# estop_rx.net
KiCad netlist of a schematic drawn in EAGLE
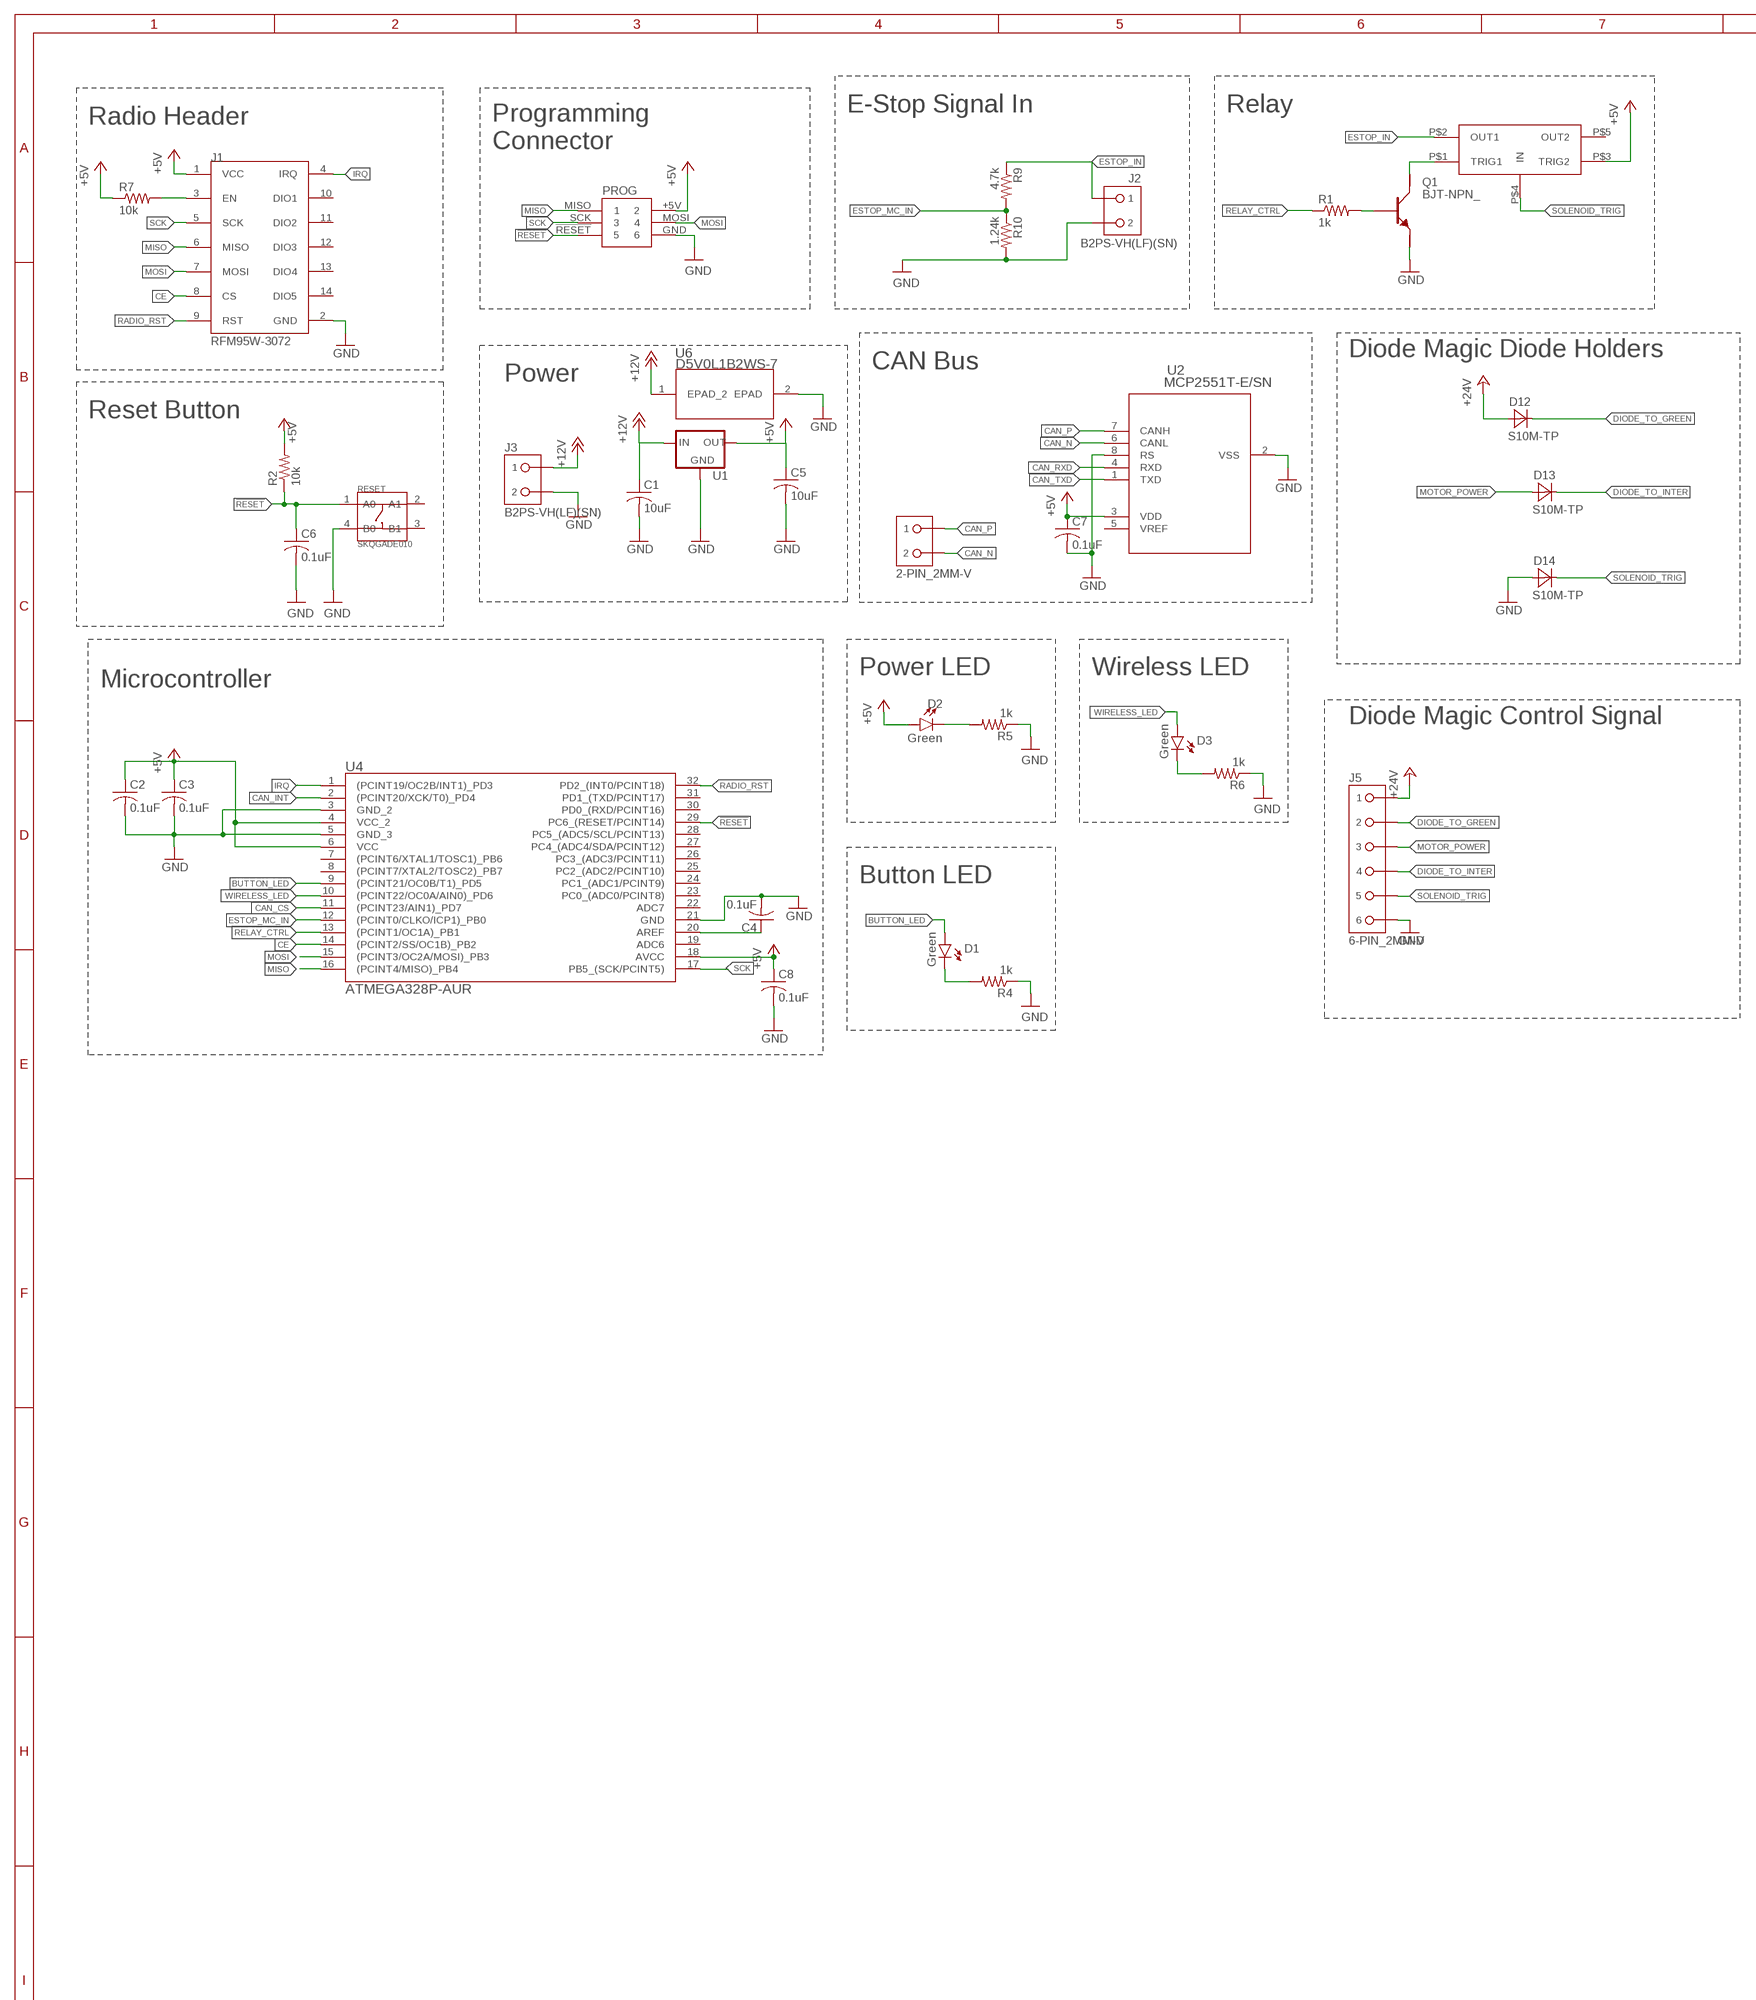
[diagram p0: schematic, sheet 1, part 1 of 2]
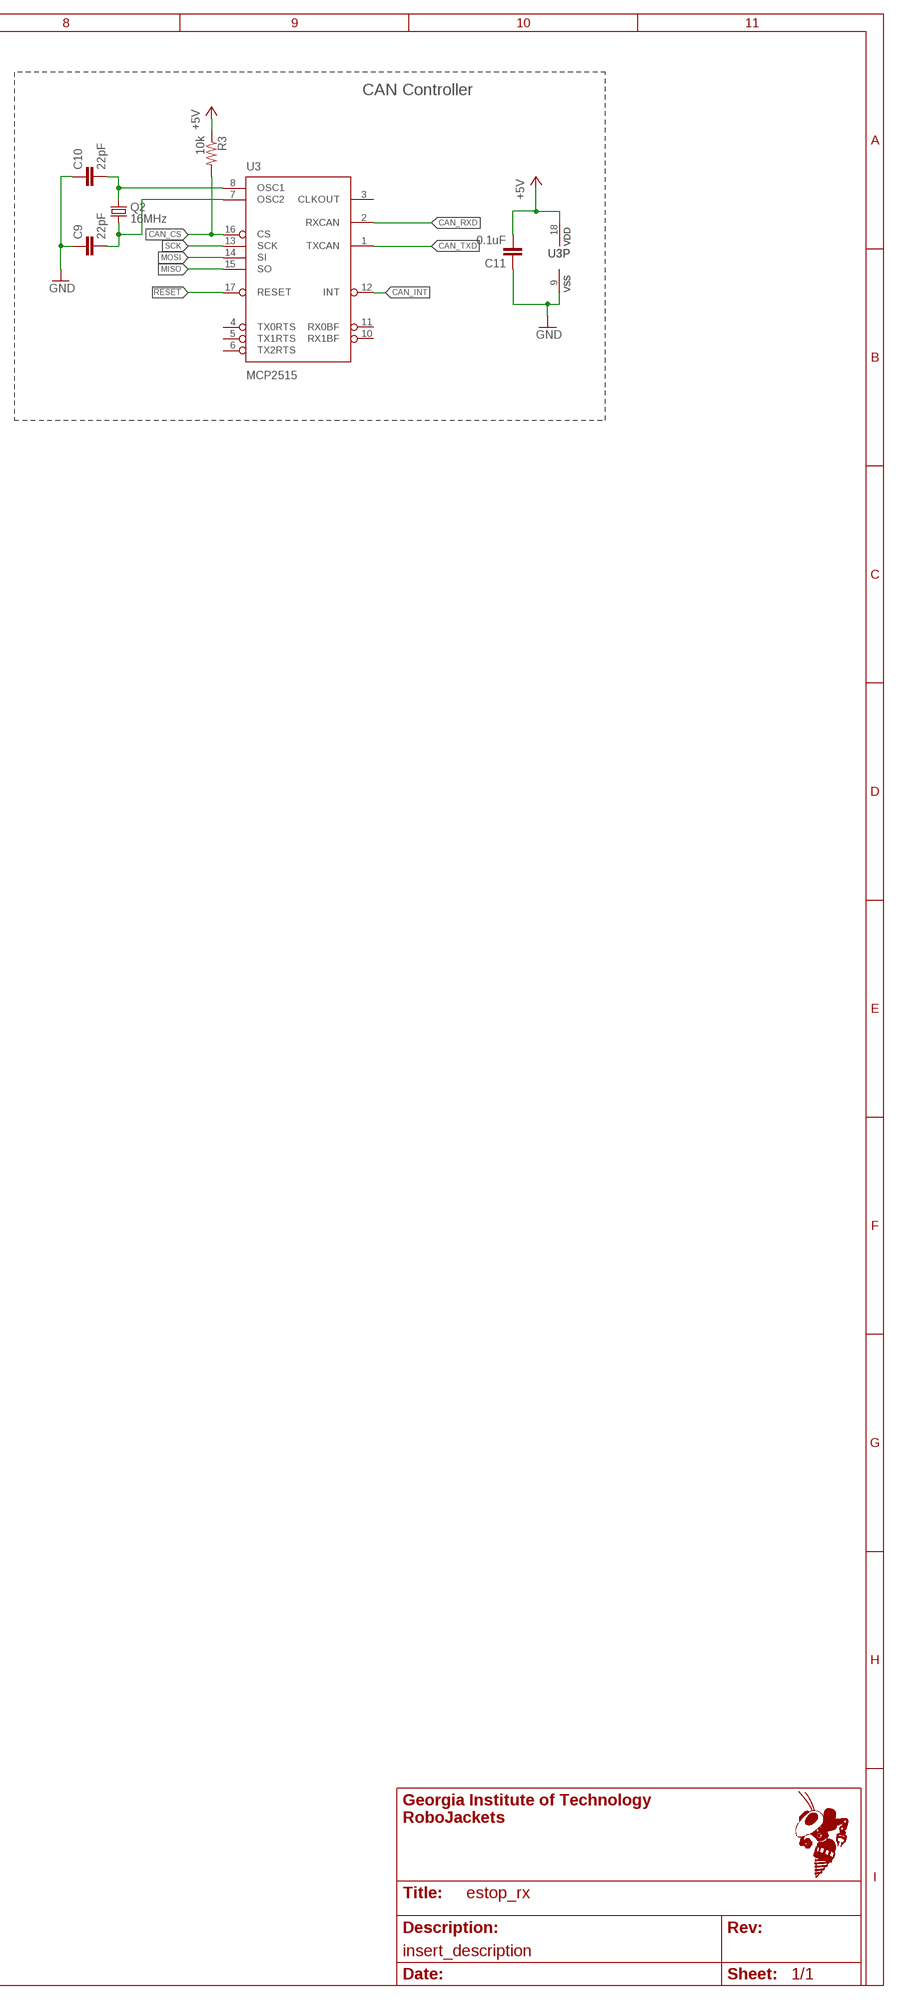
[diagram p1: schematic, sheet 1, part 2 of 2]

(export (version "E")
  (design (tool "Eeschema 10.0.6"))
  (components
    (comp (ref "C1")
      (value "10uF")
      (footprint "eagle-import:C0805")
      (libsource (lib "eagle-import") (part "C-USC0805"))
    )
    (comp (ref "C2")
      (value "0.1uF")
      (footprint "eagle-import:C0603")
      (libsource (lib "eagle-import") (part "C-USC0603"))
    )
    (comp (ref "C3")
      (value "0.1uF")
      (footprint "eagle-import:C0603")
      (libsource (lib "eagle-import") (part "C-USC0603"))
    )
    (comp (ref "C4")
      (value "0.1uF")
      (footprint "eagle-import:C0603")
      (libsource (lib "eagle-import") (part "C-USC0603"))
    )
    (comp (ref "C5")
      (value "10uF")
      (footprint "eagle-import:C0805")
      (libsource (lib "eagle-import") (part "C-USC0805"))
    )
    (comp (ref "C6")
      (value "0.1uF")
      (footprint "eagle-import:C0603")
      (libsource (lib "eagle-import") (part "resistor_348_C-USC0603"))
    )
    (comp (ref "C7")
      (value "0.1uF")
      (footprint "eagle-import:C0603")
      (libsource (lib "eagle-import") (part "C-USC0603"))
    )
    (comp (ref "C8")
      (value "0.1uF")
      (footprint "eagle-import:C0603")
      (libsource (lib "eagle-import") (part "C-USC0603"))
    )
    (comp (ref "C9")
      (value "22pF")
      (footprint "eagle-import:0603-CAP")
      (libsource (lib "eagle-import") (part "22PF-50V-5%(0603)"))
    )
    (comp (ref "C10")
      (value "22pF")
      (footprint "eagle-import:0603-CAP")
      (libsource (lib "eagle-import") (part "22PF-50V-5%(0603)"))
    )
    (comp (ref "C11")
      (value "0.1uF")
      (footprint "eagle-import:0603-CAP")
      (libsource (lib "eagle-import") (part "0.1UF-25V(+80/-20%)(0603)"))
    )
    (comp (ref "D1")
      (value "Green")
      (footprint "eagle-import:LED-0603")
      (libsource (lib "eagle-import") (part "LED-YELLOW0603"))
    )
    (comp (ref "D2")
      (value "Green")
      (footprint "eagle-import:LED-0603")
      (libsource (lib "eagle-import") (part "LED-YELLOW0603"))
    )
    (comp (ref "D3")
      (value "Green")
      (footprint "eagle-import:LED-0603")
      (libsource (lib "eagle-import") (part "LED-YELLOW0603"))
    )
    (comp (ref "D12")
      (value "S10M-TP")
      (footprint "eagle-import:SMC")
      (libsource (lib "eagle-import") (part "S10M-TP"))
    )
    (comp (ref "D13")
      (value "S10M-TP")
      (footprint "eagle-import:SMC")
      (libsource (lib "eagle-import") (part "S10M-TP"))
    )
    (comp (ref "D14")
      (value "S10M-TP")
      (footprint "eagle-import:SMC")
      (libsource (lib "eagle-import") (part "S10M-TP"))
    )
    (comp (ref "J1")
      (value "RFM95W-3072")
      (footprint "eagle-import:RFM95W-3072")
      (libsource (lib "eagle-import") (part "RFM95W-3072"))
    )
    (comp (ref "J2")
      (value "B2PS-VH(LF)(SN)")
      (footprint "eagle-import:B2PS-CENTERED")
      (libsource (lib "eagle-import") (part "B2P?-VH(LF)(SN)S"))
    )
    (comp (ref "J3")
      (value "B2PS-VH(LF)(SN)")
      (footprint "eagle-import:B2PS-CENTERED")
      (libsource (lib "eagle-import") (part "B2P?-VH(LF)(SN)S"))
    )
    (comp (ref "J4")
      (value "2-PIN_2MM-V")
      (footprint "eagle-import:2MM-2-V")
      (libsource (lib "eagle-import") (part "2-PIN_2MM-V"))
    )
    (comp (ref "J5")
      (value "6-PIN_2MM-V")
      (footprint "eagle-import:2MM-6-V")
      (libsource (lib "eagle-import") (part "6-PIN_2MM-V"))
    )
    (comp (ref "PROG")
      (value "ICSP Connector")
      (footprint "eagle-import:2X3SHROUDED")
      (libsource (lib "eagle-import") (part "2X3SHROUDED"))
    )
    (comp (ref "Q1")
      (value "BJT-NPN_")
      (footprint "eagle-import:SOT-23-3")
      (libsource (lib "eagle-import") (part "BJT-NPN_"))
    )
    (comp (ref "Q2")
      (value "16MHz")
      (footprint "eagle-import:CRYSTAL-SMD-5X3")
      (libsource (lib "eagle-import") (part "CRYSTAL5X3"))
    )
    (comp (ref "R1")
      (value "1k")
      (footprint "eagle-import:R0603")
      (libsource (lib "eagle-import") (part "R-US_R0603"))
    )
    (comp (ref "R2")
      (value "10k")
      (footprint "eagle-import:R0603")
      (libsource (lib "eagle-import") (part "R-US_R0603"))
    )
    (comp (ref "R3")
      (value "10k")
      (footprint "eagle-import:R0603")
      (libsource (lib "eagle-import") (part "resistor_348_R-US_R0603"))
    )
    (comp (ref "R4")
      (value "1k")
      (footprint "eagle-import:R0603")
      (libsource (lib "eagle-import") (part "resistor_348_R-US_R0603"))
    )
    (comp (ref "R5")
      (value "1k")
      (footprint "eagle-import:R0603")
      (libsource (lib "eagle-import") (part "resistor_348_R-US_R0603"))
    )
    (comp (ref "R6")
      (value "1k")
      (footprint "eagle-import:R0603")
      (libsource (lib "eagle-import") (part "resistor_348_R-US_R0603"))
    )
    (comp (ref "R7")
      (value "10k")
      (footprint "eagle-import:R0603")
      (libsource (lib "eagle-import") (part "R-US_R0603"))
    )
    (comp (ref "R9")
      (value "4.7k")
      (footprint "eagle-import:R0603")
      (libsource (lib "eagle-import") (part "resistor_348_R-US_R0603"))
    )
    (comp (ref "R10")
      (value "1.24k")
      (footprint "eagle-import:R0603")
      (libsource (lib "eagle-import") (part "resistor_348_R-US_R0603"))
    )
    (comp (ref "RESET")
      (value "SKQGADE010")
      (footprint "eagle-import:SW4-SMD-5.2X5.2X1.5MM")
      (libsource (lib "eagle-import") (part "SMD-SWITCH-TOP-260GF(4P-D5.2MM)"))
    )
    (comp (ref "U$1")
      (value "G5LE-14")
      (footprint "eagle-import:G5LE-14")
      (libsource (lib "eagle-import") (part "G5LE-14"))
    )
    (comp (ref "U1")
      (value "R-78E5.0-1.0CONV_R-78E5.0-1.0")
      (footprint "eagle-import:CONV_R-78E5.0-1.0")
      (libsource (lib "eagle-import") (part "R-78E5.0-1.0CONV_R-78E5.0-1.0"))
    )
    (comp (ref "U2")
      (value "MCP2551T-E/SN")
      (footprint "eagle-import:SOIC8-N_MC")
      (fields (field (name "MANUFACTURER_PART_NUMBER") "MCP2551TESN"))
      (libsource (lib "eagle-import") (part "MCP2551T-E/SN"))
    )
    (comp (ref "U3")
      (value "MCP2515")
      (footprint "eagle-import:SO-18W")
      (libsource (lib "eagle-import") (part "MCP2510SO"))
    )
    (comp (ref "U4")
      (value "ATMEGA328P-AUR")
      (footprint "eagle-import:ATMEGA328P-AUR")
      (libsource (lib "eagle-import") (part "ATMEGA328P-AUR"))
    )
    (comp (ref "U6")
      (value "D5V0L1B2WS-7")
      (footprint "eagle-import:SOD323")
      (libsource (lib "eagle-import") (part "D5V0L1B2WS-7"))
    )
  )
  (nets
    (net (code "1") (name "+5V") (class "Default")
      (node (ref "C11") (pin "2") (pinfunction "2_2") (pintype "passive"))
      (node (ref "C2") (pin "1") (pinfunction "1_1") (pintype "passive"))
      (node (ref "C3") (pin "1") (pinfunction "1_1") (pintype "passive"))
      (node (ref "C5") (pin "1") (pinfunction "1_1") (pintype "passive"))
      (node (ref "C7") (pin "1") (pinfunction "1_1") (pintype "passive"))
      (node (ref "C8") (pin "1") (pinfunction "1_1") (pintype "passive"))
      (node (ref "D2") (pin "A") (pinfunction "A_A") (pintype "passive"))
      (node (ref "J1") (pin "1") (pinfunction "VCC_1") (pintype "passive"))
      (node (ref "PROG") (pin "+5V") (pinfunction "2_+5V") (pintype "bidirectional"))
      (node (ref "R2") (pin "2") (pinfunction "2_2") (pintype "passive"))
      (node (ref "R3") (pin "1") (pinfunction "1_1") (pintype "passive"))
      (node (ref "R7") (pin "1") (pinfunction "1_1") (pintype "passive"))
      (node (ref "U$1") (pin "P$3") (pinfunction "TRIG2_P$3") (pintype "bidirectional"))
      (node (ref "U1") (pin "3") (pinfunction "OUT_3") (pintype "passive"))
      (node (ref "U2") (pin "3") (pinfunction "VDD_3") (pintype "passive"))
      (node (ref "U3") (pin "18") (pinfunction "VDD_18") (pintype "power_in"))
      (node (ref "U4") (pin "18") (pinfunction "AVCC_18") (pintype "bidirectional"))
      (node (ref "U4") (pin "4") (pinfunction "VCC_2_4") (pintype "bidirectional"))
      (node (ref "U4") (pin "6") (pinfunction "VCC_6") (pintype "bidirectional"))
    )
    (net (code "2") (name "+12V") (class "Default")
      (node (ref "C1") (pin "1") (pinfunction "1_1") (pintype "passive"))
      (node (ref "J3") (pin "1") (pinfunction "1_1") (pintype "bidirectional"))
      (node (ref "U1") (pin "1") (pinfunction "IN_1") (pintype "input"))
      (node (ref "U6") (pin "1") (pinfunction "EPAD_2_1") (pintype "passive"))
    )
    (net (code "3") (name "+24V") (class "Default")
      (node (ref "D12") (pin "A") (pinfunction "A_A") (pintype "passive"))
      (node (ref "J5") (pin "1") (pinfunction "1_1") (pintype "passive"))
    )
    (net (code "4") (name "/~{RESET}") (class "Default")
      (node (ref "C6") (pin "1") (pinfunction "1_1") (pintype "passive"))
      (node (ref "PROG") (pin "!RESET") (pinfunction "5_!RESET") (pintype "bidirectional"))
      (node (ref "R2") (pin "1") (pinfunction "1_1") (pintype "passive"))
      (node (ref "RESET") (pin "1") (pinfunction "A0_1") (pintype "bidirectional"))
      (node (ref "U3") (pin "17") (pinfunction "RESET_17") (pintype "input"))
      (node (ref "U4") (pin "29") (pinfunction "PC6_(RESET/PCINT14)_29") (pintype "bidirectional"))
    )
    (net (code "5") (name "BUTTON_LED") (class "Default")
      (node (ref "D1") (pin "A") (pinfunction "A_A") (pintype "passive"))
      (node (ref "U4") (pin "9") (pinfunction "(PCINT21/OC0B/T1)_PD5_9") (pintype "bidirectional"))
    )
    (net (code "6") (name "CAN_CS") (class "Default")
      (node (ref "R3") (pin "2") (pinfunction "2_2") (pintype "passive"))
      (node (ref "U3") (pin "16") (pinfunction "CS_16") (pintype "input"))
      (node (ref "U4") (pin "11") (pinfunction "(PCINT23/AIN1)_PD7_11") (pintype "bidirectional"))
    )
    (net (code "7") (name "CAN_INT") (class "Default")
      (node (ref "U3") (pin "12") (pinfunction "INT_12") (pintype "output"))
      (node (ref "U4") (pin "2") (pinfunction "(PCINT20/XCK/T0)_PD4_2") (pintype "bidirectional"))
    )
    (net (code "8") (name "CAN_N") (class "Default")
      (node (ref "J4") (pin "2") (pinfunction "2_2") (pintype "bidirectional"))
      (node (ref "U2") (pin "6") (pinfunction "CANL_6") (pintype "passive"))
    )
    (net (code "9") (name "CAN_P") (class "Default")
      (node (ref "J4") (pin "1") (pinfunction "1_1") (pintype "bidirectional"))
      (node (ref "U2") (pin "7") (pinfunction "CANH_7") (pintype "passive"))
    )
    (net (code "10") (name "CAN_RXD") (class "Default")
      (node (ref "U2") (pin "4") (pinfunction "RXD_4") (pintype "passive"))
      (node (ref "U3") (pin "2") (pinfunction "RXCAN_2") (pintype "input"))
    )
    (net (code "11") (name "CAN_TXD") (class "Default")
      (node (ref "U2") (pin "1") (pinfunction "TXD_1") (pintype "passive"))
      (node (ref "U3") (pin "1") (pinfunction "TXCAN_1") (pintype "output"))
    )
    (net (code "12") (name "CE") (class "Default")
      (node (ref "J1") (pin "8") (pinfunction "CS_8") (pintype "passive"))
      (node (ref "U4") (pin "14") (pinfunction "(PCINT2/SS/OC1B)_PB2_14") (pintype "bidirectional"))
    )
    (net (code "13") (name "DIODE_TO_GREEN") (class "Default")
      (node (ref "D12") (pin "C") (pinfunction "C_C") (pintype "passive"))
      (node (ref "J5") (pin "2") (pinfunction "2_2") (pintype "passive"))
    )
    (net (code "14") (name "DIODE_TO_INTER") (class "Default")
      (node (ref "D13") (pin "C") (pinfunction "C_C") (pintype "passive"))
      (node (ref "J5") (pin "4") (pinfunction "4_4") (pintype "passive"))
    )
    (net (code "15") (name "ESTOP_IN") (class "Default")
      (node (ref "J2") (pin "1") (pinfunction "1_1") (pintype "bidirectional"))
      (node (ref "R9") (pin "1") (pinfunction "1_1") (pintype "passive"))
      (node (ref "U$1") (pin "P$2") (pinfunction "OUT1_P$2") (pintype "bidirectional"))
    )
    (net (code "16") (name "ESTOP_MC_IN") (class "Default")
      (node (ref "R10") (pin "1") (pinfunction "1_1") (pintype "passive"))
      (node (ref "R9") (pin "2") (pinfunction "2_2") (pintype "passive"))
      (node (ref "U4") (pin "12") (pinfunction "(PCINT0/CLKO/ICP1)_PB0_12") (pintype "bidirectional"))
    )
    (net (code "17") (name "GND") (class "Default")
      (node (ref "C1") (pin "2") (pinfunction "2_2") (pintype "passive"))
      (node (ref "C10") (pin "1") (pinfunction "1_1") (pintype "passive"))
      (node (ref "C11") (pin "1") (pinfunction "1_1") (pintype "passive"))
      (node (ref "C2") (pin "2") (pinfunction "2_2") (pintype "passive"))
      (node (ref "C3") (pin "2") (pinfunction "2_2") (pintype "passive"))
      (node (ref "C4") (pin "2") (pinfunction "2_2") (pintype "passive"))
      (node (ref "C5") (pin "2") (pinfunction "2_2") (pintype "passive"))
      (node (ref "C6") (pin "2") (pinfunction "2_2") (pintype "passive"))
      (node (ref "C7") (pin "2") (pinfunction "2_2") (pintype "passive"))
      (node (ref "C8") (pin "2") (pinfunction "2_2") (pintype "passive"))
      (node (ref "C9") (pin "1") (pinfunction "1_1") (pintype "passive"))
      (node (ref "D14") (pin "A") (pinfunction "A_A") (pintype "passive"))
      (node (ref "J1") (pin "2") (pinfunction "GND_2") (pintype "passive"))
      (node (ref "J2") (pin "2") (pinfunction "2_2") (pintype "bidirectional"))
      (node (ref "J3") (pin "2") (pinfunction "2_2") (pintype "bidirectional"))
      (node (ref "J5") (pin "6") (pinfunction "6_6") (pintype "passive"))
      (node (ref "PROG") (pin "GND") (pinfunction "6_GND") (pintype "bidirectional"))
      (node (ref "Q1") (pin "2") (pinfunction "E_2") (pintype "bidirectional"))
      (node (ref "R10") (pin "2") (pinfunction "2_2") (pintype "passive"))
      (node (ref "R4") (pin "1") (pinfunction "1_1") (pintype "passive"))
      (node (ref "R5") (pin "1") (pinfunction "1_1") (pintype "passive"))
      (node (ref "R6") (pin "1") (pinfunction "1_1") (pintype "passive"))
      (node (ref "RESET") (pin "4") (pinfunction "B0_4") (pintype "bidirectional"))
      (node (ref "U1") (pin "2") (pinfunction "GND_2") (pintype "input"))
      (node (ref "U2") (pin "2") (pinfunction "VSS_2") (pintype "passive"))
      (node (ref "U2") (pin "8") (pinfunction "RS_8") (pintype "passive"))
      (node (ref "U3") (pin "9") (pinfunction "VSS_9") (pintype "power_in"))
      (node (ref "U4") (pin "21") (pinfunction "GND_21") (pintype "bidirectional"))
      (node (ref "U4") (pin "3") (pinfunction "GND_2_3") (pintype "bidirectional"))
      (node (ref "U4") (pin "5") (pinfunction "GND_3_5") (pintype "bidirectional"))
      (node (ref "U6") (pin "2") (pinfunction "EPAD_2") (pintype "passive"))
    )
    (net (code "18") (name "IRQ") (class "Default")
      (node (ref "J1") (pin "4") (pinfunction "IRQ_4") (pintype "passive"))
      (node (ref "U4") (pin "1") (pinfunction "(PCINT19/OC2B/INT1)_PD3_1") (pintype "bidirectional"))
    )
    (net (code "19") (name "MISO") (class "Default")
      (node (ref "J1") (pin "6") (pinfunction "MISO_6") (pintype "passive"))
      (node (ref "PROG") (pin "MISO") (pinfunction "1_MISO") (pintype "bidirectional"))
      (node (ref "U3") (pin "15") (pinfunction "SO_15") (pintype "output"))
      (node (ref "U4") (pin "16") (pinfunction "(PCINT4/MISO)_PB4_16") (pintype "bidirectional"))
    )
    (net (code "20") (name "MOSI") (class "Default")
      (node (ref "J1") (pin "7") (pinfunction "MOSI_7") (pintype "passive"))
      (node (ref "PROG") (pin "MOSI") (pinfunction "4_MOSI") (pintype "bidirectional"))
      (node (ref "U3") (pin "14") (pinfunction "SI_14") (pintype "input"))
      (node (ref "U4") (pin "15") (pinfunction "(PCINT3/OC2A/MOSI)_PB3_15") (pintype "bidirectional"))
    )
    (net (code "21") (name "MOTOR_POWER") (class "Default")
      (node (ref "D13") (pin "A") (pinfunction "A_A") (pintype "passive"))
      (node (ref "J5") (pin "3") (pinfunction "3_3") (pintype "passive"))
    )
    (net (code "22") (name "Net-(D1-PadC)") (class "Default")
      (node (ref "D1") (pin "C") (pinfunction "C_C") (pintype "passive"))
      (node (ref "R4") (pin "2") (pinfunction "2_2") (pintype "passive"))
    )
    (net (code "23") (name "Net-(D2-PadC)") (class "Default")
      (node (ref "D2") (pin "C") (pinfunction "C_C") (pintype "passive"))
      (node (ref "R5") (pin "2") (pinfunction "2_2") (pintype "passive"))
    )
    (net (code "24") (name "Net-(D3-PadC)") (class "Default")
      (node (ref "D3") (pin "C") (pinfunction "C_C") (pintype "passive"))
      (node (ref "R6") (pin "2") (pinfunction "2_2") (pintype "passive"))
    )
    (net (code "25") (name "Net-(J1-EN)") (class "Default")
      (node (ref "J1") (pin "3") (pinfunction "EN_3") (pintype "passive"))
      (node (ref "R7") (pin "2") (pinfunction "2_2") (pintype "passive"))
    )
    (net (code "26") (name "Net-(Q1-B)") (class "Default")
      (node (ref "Q1") (pin "1") (pinfunction "B_1") (pintype "bidirectional"))
      (node (ref "R1") (pin "2") (pinfunction "2_2") (pintype "passive"))
    )
    (net (code "27") (name "Net-(Q1-C)") (class "Default")
      (node (ref "Q1") (pin "3") (pinfunction "C_3") (pintype "bidirectional"))
      (node (ref "U$1") (pin "P$1") (pinfunction "TRIG1_P$1") (pintype "bidirectional"))
    )
    (net (code "28") (name "Net-(Q2-2)") (class "Default")
      (node (ref "C10") (pin "2") (pinfunction "2_2") (pintype "passive"))
      (node (ref "Q2") (pin "3") (pinfunction "2_3") (pintype "passive"))
      (node (ref "U3") (pin "8") (pinfunction "OSC1_8") (pintype "input"))
    )
    (net (code "29") (name "Net-(U3A-OSC2)") (class "Default")
      (node (ref "C9") (pin "2") (pinfunction "2_2") (pintype "passive"))
      (node (ref "Q2") (pin "1") (pinfunction "1_1") (pintype "passive"))
      (node (ref "U3") (pin "7") (pinfunction "OSC2_7") (pintype "output"))
    )
    (net (code "30") (name "Net-(U4-AREF)") (class "Default")
      (node (ref "C4") (pin "1") (pinfunction "1_1") (pintype "passive"))
      (node (ref "U4") (pin "20") (pinfunction "AREF_20") (pintype "bidirectional"))
    )
    (net (code "31") (name "RADIO_RST") (class "Default")
      (node (ref "J1") (pin "9") (pinfunction "RST_9") (pintype "passive"))
      (node (ref "U4") (pin "32") (pinfunction "PD2_(INT0/PCINT18)_32") (pintype "bidirectional"))
    )
    (net (code "32") (name "RELAY_CTRL") (class "Default")
      (node (ref "R1") (pin "1") (pinfunction "1_1") (pintype "passive"))
      (node (ref "U4") (pin "13") (pinfunction "(PCINT1/OC1A)_PB1_13") (pintype "bidirectional"))
    )
    (net (code "33") (name "SCK") (class "Default")
      (node (ref "J1") (pin "5") (pinfunction "SCK_5") (pintype "passive"))
      (node (ref "PROG") (pin "SCK") (pinfunction "3_SCK") (pintype "bidirectional"))
      (node (ref "U3") (pin "13") (pinfunction "SCK_13") (pintype "input"))
      (node (ref "U4") (pin "17") (pinfunction "PB5_(SCK/PCINT5)_17") (pintype "bidirectional"))
    )
    (net (code "34") (name "SOLENOID_TRIG") (class "Default")
      (node (ref "D14") (pin "C") (pinfunction "C_C") (pintype "passive"))
      (node (ref "J5") (pin "5") (pinfunction "5_5") (pintype "passive"))
      (node (ref "U$1") (pin "P$4") (pinfunction "IN_P$4") (pintype "bidirectional"))
    )
    (net (code "35") (name "WIRELESS_LED") (class "Default")
      (node (ref "D3") (pin "A") (pinfunction "A_A") (pintype "passive"))
      (node (ref "U4") (pin "10") (pinfunction "(PCINT22/OC0A/AIN0)_PD6_10") (pintype "bidirectional"))
    )
    (net (code "36") (name "unconnected-(J1-DIO1-Pad10)") (class "Default")
      (node (ref "J1") (pin "10") (pinfunction "DIO1_10") (pintype "bidirectional"))
    )
    (net (code "37") (name "unconnected-(J1-DIO2-Pad11)") (class "Default")
      (node (ref "J1") (pin "11") (pinfunction "DIO2_11") (pintype "bidirectional"))
    )
    (net (code "38") (name "unconnected-(J1-DIO3-Pad12)") (class "Default")
      (node (ref "J1") (pin "12") (pinfunction "DIO3_12") (pintype "bidirectional"))
    )
    (net (code "39") (name "unconnected-(J1-DIO4-Pad13)") (class "Default")
      (node (ref "J1") (pin "13") (pinfunction "DIO4_13") (pintype "bidirectional"))
    )
    (net (code "40") (name "unconnected-(J1-DIO5-Pad14)") (class "Default")
      (node (ref "J1") (pin "14") (pinfunction "DIO5_14") (pintype "bidirectional"))
    )
    (net (code "41") (name "unconnected-(RESET-A1-Pad2)") (class "Default")
      (node (ref "RESET") (pin "2") (pinfunction "A1_2") (pintype "bidirectional"))
    )
    (net (code "42") (name "unconnected-(RESET-B1-Pad3)") (class "Default")
      (node (ref "RESET") (pin "3") (pinfunction "B1_3") (pintype "bidirectional"))
    )
    (net (code "43") (name "unconnected-(U$1-OUT2-PadP$5)") (class "Default")
      (node (ref "U$1") (pin "P$5") (pinfunction "OUT2_P$5") (pintype "bidirectional"))
    )
    (net (code "44") (name "unconnected-(U2-VREF-Pad5)") (class "Default")
      (node (ref "U2") (pin "5") (pinfunction "VREF_5") (pintype "passive"))
    )
    (net (code "45") (name "unconnected-(U3A-CLKOUT-Pad3)") (class "Default")
      (node (ref "U3") (pin "3") (pinfunction "CLKOUT_3") (pintype "output"))
    )
    (net (code "46") (name "unconnected-(U3A-RX0BF-Pad11)") (class "Default")
      (node (ref "U3") (pin "11") (pinfunction "RX0BF_11") (pintype "output"))
    )
    (net (code "47") (name "unconnected-(U3A-RX1BF-Pad10)") (class "Default")
      (node (ref "U3") (pin "10") (pinfunction "RX1BF_10") (pintype "output"))
    )
    (net (code "48") (name "unconnected-(U3A-TX0RTS-Pad4)") (class "Default")
      (node (ref "U3") (pin "4") (pinfunction "TX0RTS_4") (pintype "input"))
    )
    (net (code "49") (name "unconnected-(U3A-TX1RTS-Pad5)") (class "Default")
      (node (ref "U3") (pin "5") (pinfunction "TX1RTS_5") (pintype "input"))
    )
    (net (code "50") (name "unconnected-(U3A-TX2RTS-Pad6)") (class "Default")
      (node (ref "U3") (pin "6") (pinfunction "TX2RTS_6") (pintype "input"))
    )
    (net (code "51") (name "unconnected-(U4-(PCINT6{slash}XTAL1{slash}TOSC1)_PB6-Pad7)") (class "Default")
      (node (ref "U4") (pin "7") (pinfunction "(PCINT6/XTAL1/TOSC1)_PB6_7") (pintype "bidirectional"))
    )
    (net (code "52") (name "unconnected-(U4-(PCINT7{slash}XTAL2{slash}TOSC2)_PB7-Pad8)") (class "Default")
      (node (ref "U4") (pin "8") (pinfunction "(PCINT7/XTAL2/TOSC2)_PB7_8") (pintype "bidirectional"))
    )
    (net (code "53") (name "unconnected-(U4-ADC6-Pad19)") (class "Default")
      (node (ref "U4") (pin "19") (pinfunction "ADC6_19") (pintype "bidirectional"))
    )
    (net (code "54") (name "unconnected-(U4-ADC7-Pad22)") (class "Default")
      (node (ref "U4") (pin "22") (pinfunction "ADC7_22") (pintype "bidirectional"))
    )
    (net (code "55") (name "unconnected-(U4-PC0_(ADC0{slash}PCINT8)-Pad23)") (class "Default")
      (node (ref "U4") (pin "23") (pinfunction "PC0_(ADC0/PCINT8)_23") (pintype "bidirectional"))
    )
    (net (code "56") (name "unconnected-(U4-PC1_(ADC1{slash}PCINT9)-Pad24)") (class "Default")
      (node (ref "U4") (pin "24") (pinfunction "PC1_(ADC1/PCINT9)_24") (pintype "bidirectional"))
    )
    (net (code "57") (name "unconnected-(U4-PC2_(ADC2{slash}PCINT10)-Pad25)") (class "Default")
      (node (ref "U4") (pin "25") (pinfunction "PC2_(ADC2/PCINT10)_25") (pintype "bidirectional"))
    )
    (net (code "58") (name "unconnected-(U4-PC3_(ADC3{slash}PCINT11)-Pad26)") (class "Default")
      (node (ref "U4") (pin "26") (pinfunction "PC3_(ADC3/PCINT11)_26") (pintype "bidirectional"))
    )
    (net (code "59") (name "unconnected-(U4-PC4_(ADC4{slash}SDA{slash}PCINT12)-Pad27)") (class "Default")
      (node (ref "U4") (pin "27") (pinfunction "PC4_(ADC4/SDA/PCINT12)_27") (pintype "bidirectional"))
    )
    (net (code "60") (name "unconnected-(U4-PC5_(ADC5{slash}SCL{slash}PCINT13)-Pad28)") (class "Default")
      (node (ref "U4") (pin "28") (pinfunction "PC5_(ADC5/SCL/PCINT13)_28") (pintype "bidirectional"))
    )
    (net (code "61") (name "unconnected-(U4-PD0_(RXD{slash}PCINT16)-Pad30)") (class "Default")
      (node (ref "U4") (pin "30") (pinfunction "PD0_(RXD/PCINT16)_30") (pintype "bidirectional"))
    )
    (net (code "62") (name "unconnected-(U4-PD1_(TXD{slash}PCINT17)-Pad31)") (class "Default")
      (node (ref "U4") (pin "31") (pinfunction "PD1_(TXD/PCINT17)_31") (pintype "bidirectional"))
    )
  )
)
